# ot3m_bt_smd.net
KiCad netlist of a schematic drawn in EAGLE
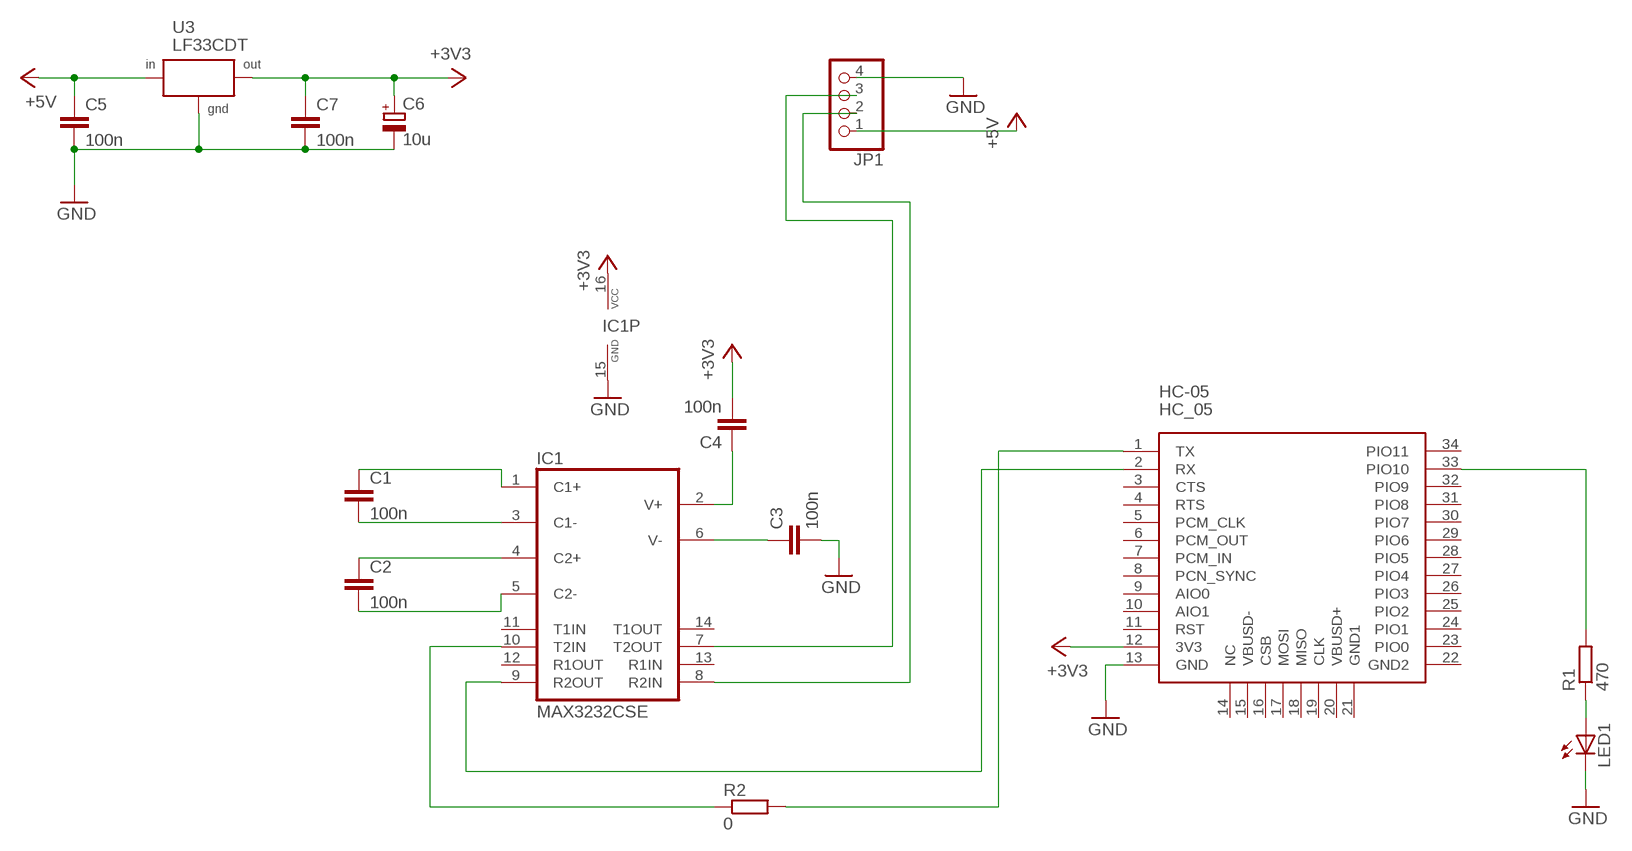
[diagram p0: schematic, sheet 1]

(export (version "E")
  (design (tool "Eeschema 10.0.6"))
  (components
    (comp (ref "C1")
      (value "100n")
      (footprint "eagle-import:C0805")
      (libsource (lib "eagle-import") (part "C-EUC0805"))
    )
    (comp (ref "C2")
      (value "100n")
      (footprint "eagle-import:C0805")
      (libsource (lib "eagle-import") (part "C-EUC0805"))
    )
    (comp (ref "C3")
      (value "100n")
      (footprint "eagle-import:C0805")
      (libsource (lib "eagle-import") (part "C-EUC0805"))
    )
    (comp (ref "C4")
      (value "100n")
      (footprint "eagle-import:C0805")
      (libsource (lib "eagle-import") (part "C-EUC0805"))
    )
    (comp (ref "C5")
      (value "100n")
      (footprint "eagle-import:C0805")
      (libsource (lib "eagle-import") (part "C-EUC0805"))
    )
    (comp (ref "C6")
      (value "10u")
      (footprint "eagle-import:PANASONIC_B")
      (libsource (lib "eagle-import") (part "CPOL-EUB"))
    )
    (comp (ref "C7")
      (value "100n")
      (footprint "eagle-import:C0805")
      (libsource (lib "eagle-import") (part "C-EUC0805"))
    )
    (comp (ref "HC-05")
      (value "HC_05")
      (footprint "eagle-import:BLUETOOTH_SMD")
      (libsource (lib "eagle-import") (part "HC_05"))
    )
    (comp (ref "IC1")
      (value "MAX3232CSE")
      (footprint "eagle-import:SO16")
      (libsource (lib "eagle-import") (part "MAX3232SEC"))
    )
    (comp (ref "JP1")
      (value "PINHD-1X4/90")
      (footprint "eagle-import:1X04_90")
      (libsource (lib "eagle-import") (part "PINHD-1X4/90"))
    )
    (comp (ref "LED1")
      (value "LEDCHIP-LED0805")
      (footprint "eagle-import:CHIP-LED0805")
      (libsource (lib "eagle-import") (part "LEDCHIP-LED0805"))
    )
    (comp (ref "R1")
      (value "470")
      (footprint "eagle-import:M0805")
      (libsource (lib "eagle-import") (part "R-EU_M0805"))
    )
    (comp (ref "R2")
      (value "0")
      (footprint "eagle-import:M0805")
      (libsource (lib "eagle-import") (part "R-EU_M0805"))
    )
    (comp (ref "U3")
      (value "LF33CDT")
      (footprint "eagle-import:DPACK")
      (fields (field (name "MPN") "LF33CDT-TR"))
      (libsource (lib "eagle-import") (part "LF33_TO252"))
    )
  )
  (nets
    (net (code "1") (name "+3V3") (class "Default")
      (node (ref "C4") (pin "2") (pinfunction "2_2") (pintype "passive"))
      (node (ref "C6") (pin "+") (pinfunction "+_+") (pintype "passive"))
      (node (ref "C7") (pin "1") (pinfunction "1_1") (pintype "passive"))
      (node (ref "HC-05") (pin "12") (pinfunction "3V3_12") (pintype "bidirectional"))
      (node (ref "IC1") (pin "16") (pinfunction "VCC_16") (pintype "power_in"))
      (node (ref "U3") (pin "3") (pinfunction "OUT_3") (pintype "bidirectional"))
    )
    (net (code "2") (name "+5V") (class "Default")
      (node (ref "C5") (pin "1") (pinfunction "1_1") (pintype "passive"))
      (node (ref "JP1") (pin "1") (pinfunction "1_1") (pintype "passive"))
      (node (ref "U3") (pin "1") (pinfunction "IN_1") (pintype "bidirectional"))
    )
    (net (code "3") (name "GND") (class "Default")
      (node (ref "C3") (pin "2") (pinfunction "2_2") (pintype "passive"))
      (node (ref "C5") (pin "2") (pinfunction "2_2") (pintype "passive"))
      (node (ref "C6") (pin "-") (pinfunction "-_-") (pintype "passive"))
      (node (ref "C7") (pin "2") (pinfunction "2_2") (pintype "passive"))
      (node (ref "HC-05") (pin "13") (pinfunction "GND_13") (pintype "bidirectional"))
      (node (ref "IC1") (pin "15") (pinfunction "GND_15") (pintype "power_in"))
      (node (ref "JP1") (pin "4") (pinfunction "4_4") (pintype "passive"))
      (node (ref "LED1") (pin "C") (pinfunction "C_C") (pintype "passive"))
      (node (ref "U3") (pin "2") (pinfunction "GND_2") (pintype "bidirectional"))
    )
    (net (code "4") (name "Net-(HC-05-PIO10)") (class "Default")
      (node (ref "HC-05") (pin "33") (pinfunction "PIO10_33") (pintype "bidirectional"))
      (node (ref "R1") (pin "2") (pinfunction "2_2") (pintype "passive"))
    )
    (net (code "5") (name "Net-(HC-05-RX)") (class "Default")
      (node (ref "HC-05") (pin "2") (pinfunction "RX_2") (pintype "bidirectional"))
      (node (ref "IC1") (pin "9") (pinfunction "R2OUT_9") (pintype "output"))
    )
    (net (code "6") (name "Net-(HC-05-TX)") (class "Default")
      (node (ref "HC-05") (pin "1") (pinfunction "TX_1") (pintype "bidirectional"))
      (node (ref "R2") (pin "2") (pinfunction "2_2") (pintype "passive"))
    )
    (net (code "7") (name "Net-(IC1A-C1+)") (class "Default")
      (node (ref "C1") (pin "1") (pinfunction "1_1") (pintype "passive"))
      (node (ref "IC1") (pin "1") (pinfunction "C1+_1") (pintype "bidirectional"))
    )
    (net (code "8") (name "Net-(IC1A-C1-)") (class "Default")
      (node (ref "C1") (pin "2") (pinfunction "2_2") (pintype "passive"))
      (node (ref "IC1") (pin "3") (pinfunction "C1-_3") (pintype "bidirectional"))
    )
    (net (code "9") (name "Net-(IC1A-C2+)") (class "Default")
      (node (ref "C2") (pin "1") (pinfunction "1_1") (pintype "passive"))
      (node (ref "IC1") (pin "4") (pinfunction "C2+_4") (pintype "bidirectional"))
    )
    (net (code "10") (name "Net-(IC1A-C2-)") (class "Default")
      (node (ref "C2") (pin "2") (pinfunction "2_2") (pintype "passive"))
      (node (ref "IC1") (pin "5") (pinfunction "C2-_5") (pintype "bidirectional"))
    )
    (net (code "11") (name "Net-(IC1A-R2IN)") (class "Default")
      (node (ref "IC1") (pin "8") (pinfunction "R2IN_8") (pintype "input"))
      (node (ref "JP1") (pin "2") (pinfunction "2_2") (pintype "passive"))
    )
    (net (code "12") (name "Net-(IC1A-T2IN)") (class "Default")
      (node (ref "IC1") (pin "10") (pinfunction "T2IN_10") (pintype "input"))
      (node (ref "R2") (pin "1") (pinfunction "1_1") (pintype "passive"))
    )
    (net (code "13") (name "Net-(IC1A-T2OUT)") (class "Default")
      (node (ref "IC1") (pin "7") (pinfunction "T2OUT_7") (pintype "output"))
      (node (ref "JP1") (pin "3") (pinfunction "3_3") (pintype "passive"))
    )
    (net (code "14") (name "Net-(IC1A-V+)") (class "Default")
      (node (ref "C4") (pin "1") (pinfunction "1_1") (pintype "passive"))
      (node (ref "IC1") (pin "2") (pinfunction "V+_2") (pintype "bidirectional"))
    )
    (net (code "15") (name "Net-(IC1A-V-)") (class "Default")
      (node (ref "C3") (pin "1") (pinfunction "1_1") (pintype "passive"))
      (node (ref "IC1") (pin "6") (pinfunction "V-_6") (pintype "bidirectional"))
    )
    (net (code "16") (name "Net-(LED1-PadA)") (class "Default")
      (node (ref "LED1") (pin "A") (pinfunction "A_A") (pintype "passive"))
      (node (ref "R1") (pin "1") (pinfunction "1_1") (pintype "passive"))
    )
    (net (code "17") (name "unconnected-(HC-05-AIO0-Pad9)") (class "Default")
      (node (ref "HC-05") (pin "9") (pinfunction "AIO0_9") (pintype "bidirectional"))
    )
    (net (code "18") (name "unconnected-(HC-05-AIO1-Pad10)") (class "Default")
      (node (ref "HC-05") (pin "10") (pinfunction "AIO1_10") (pintype "bidirectional"))
    )
    (net (code "19") (name "unconnected-(HC-05-CLK-Pad19)") (class "Default")
      (node (ref "HC-05") (pin "19") (pinfunction "CLK_19") (pintype "bidirectional"))
    )
    (net (code "20") (name "unconnected-(HC-05-CSB-Pad16)") (class "Default")
      (node (ref "HC-05") (pin "16") (pinfunction "CSB_16") (pintype "bidirectional"))
    )
    (net (code "21") (name "unconnected-(HC-05-CTS-Pad3)") (class "Default")
      (node (ref "HC-05") (pin "3") (pinfunction "CTS_3") (pintype "bidirectional"))
    )
    (net (code "22") (name "unconnected-(HC-05-GND1-Pad21)") (class "Default")
      (node (ref "HC-05") (pin "21") (pinfunction "GND1_21") (pintype "bidirectional"))
    )
    (net (code "23") (name "unconnected-(HC-05-GND2-Pad22)") (class "Default")
      (node (ref "HC-05") (pin "22") (pinfunction "GND2_22") (pintype "bidirectional"))
    )
    (net (code "24") (name "unconnected-(HC-05-MISO-Pad18)") (class "Default")
      (node (ref "HC-05") (pin "18") (pinfunction "MISO_18") (pintype "bidirectional"))
    )
    (net (code "25") (name "unconnected-(HC-05-MOSI-Pad17)") (class "Default")
      (node (ref "HC-05") (pin "17") (pinfunction "MOSI_17") (pintype "bidirectional"))
    )
    (net (code "26") (name "unconnected-(HC-05-NC-Pad14)") (class "Default")
      (node (ref "HC-05") (pin "14") (pinfunction "NC_14") (pintype "bidirectional"))
    )
    (net (code "27") (name "unconnected-(HC-05-PCM_CLK-Pad5)") (class "Default")
      (node (ref "HC-05") (pin "5") (pinfunction "PCM_CLK_5") (pintype "bidirectional"))
    )
    (net (code "28") (name "unconnected-(HC-05-PCM_IN-Pad7)") (class "Default")
      (node (ref "HC-05") (pin "7") (pinfunction "PCM_IN_7") (pintype "bidirectional"))
    )
    (net (code "29") (name "unconnected-(HC-05-PCM_OUT-Pad6)") (class "Default")
      (node (ref "HC-05") (pin "6") (pinfunction "PCM_OUT_6") (pintype "bidirectional"))
    )
    (net (code "30") (name "unconnected-(HC-05-PCN_SYNC-Pad8)") (class "Default")
      (node (ref "HC-05") (pin "8") (pinfunction "PCN_SYNC_8") (pintype "bidirectional"))
    )
    (net (code "31") (name "unconnected-(HC-05-PIO0-Pad23)") (class "Default")
      (node (ref "HC-05") (pin "23") (pinfunction "PIO0_23") (pintype "bidirectional"))
    )
    (net (code "32") (name "unconnected-(HC-05-PIO1-Pad24)") (class "Default")
      (node (ref "HC-05") (pin "24") (pinfunction "PIO1_24") (pintype "bidirectional"))
    )
    (net (code "33") (name "unconnected-(HC-05-PIO2-Pad25)") (class "Default")
      (node (ref "HC-05") (pin "25") (pinfunction "PIO2_25") (pintype "bidirectional"))
    )
    (net (code "34") (name "unconnected-(HC-05-PIO3-Pad26)") (class "Default")
      (node (ref "HC-05") (pin "26") (pinfunction "PIO3_26") (pintype "bidirectional"))
    )
    (net (code "35") (name "unconnected-(HC-05-PIO4-Pad27)") (class "Default")
      (node (ref "HC-05") (pin "27") (pinfunction "PIO4_27") (pintype "bidirectional"))
    )
    (net (code "36") (name "unconnected-(HC-05-PIO5-Pad28)") (class "Default")
      (node (ref "HC-05") (pin "28") (pinfunction "PIO5_28") (pintype "bidirectional"))
    )
    (net (code "37") (name "unconnected-(HC-05-PIO6-Pad29)") (class "Default")
      (node (ref "HC-05") (pin "29") (pinfunction "PIO6_29") (pintype "bidirectional"))
    )
    (net (code "38") (name "unconnected-(HC-05-PIO7-Pad30)") (class "Default")
      (node (ref "HC-05") (pin "30") (pinfunction "PIO7_30") (pintype "bidirectional"))
    )
    (net (code "39") (name "unconnected-(HC-05-PIO8-Pad31)") (class "Default")
      (node (ref "HC-05") (pin "31") (pinfunction "PIO8_31") (pintype "bidirectional"))
    )
    (net (code "40") (name "unconnected-(HC-05-PIO9-Pad32)") (class "Default")
      (node (ref "HC-05") (pin "32") (pinfunction "PIO9_32") (pintype "bidirectional"))
    )
    (net (code "41") (name "unconnected-(HC-05-PIO11-Pad34)") (class "Default")
      (node (ref "HC-05") (pin "34") (pinfunction "PIO11_34") (pintype "bidirectional"))
    )
    (net (code "42") (name "unconnected-(HC-05-RST-Pad11)") (class "Default")
      (node (ref "HC-05") (pin "11") (pinfunction "RST_11") (pintype "bidirectional"))
    )
    (net (code "43") (name "unconnected-(HC-05-RTS-Pad4)") (class "Default")
      (node (ref "HC-05") (pin "4") (pinfunction "RTS_4") (pintype "bidirectional"))
    )
    (net (code "44") (name "unconnected-(HC-05-VBUSD+-Pad20)") (class "Default")
      (node (ref "HC-05") (pin "20") (pinfunction "VBUSD+_20") (pintype "bidirectional"))
    )
    (net (code "45") (name "unconnected-(HC-05-VBUSD--Pad15)") (class "Default")
      (node (ref "HC-05") (pin "15") (pinfunction "VBUSD-_15") (pintype "bidirectional"))
    )
    (net (code "46") (name "unconnected-(IC1A-R1IN-Pad13)") (class "Default")
      (node (ref "IC1") (pin "13") (pinfunction "R1IN_13") (pintype "input"))
    )
    (net (code "47") (name "unconnected-(IC1A-R1OUT-Pad12)") (class "Default")
      (node (ref "IC1") (pin "12") (pinfunction "R1OUT_12") (pintype "output"))
    )
    (net (code "48") (name "unconnected-(IC1A-T1IN-Pad11)") (class "Default")
      (node (ref "IC1") (pin "11") (pinfunction "T1IN_11") (pintype "input"))
    )
    (net (code "49") (name "unconnected-(IC1A-T1OUT-Pad14)") (class "Default")
      (node (ref "IC1") (pin "14") (pinfunction "T1OUT_14") (pintype "output"))
    )
  )
)
